# Shuttler_AFE_SAS_CON.net
KiCad netlist of a schematic drawn in Altium Designer
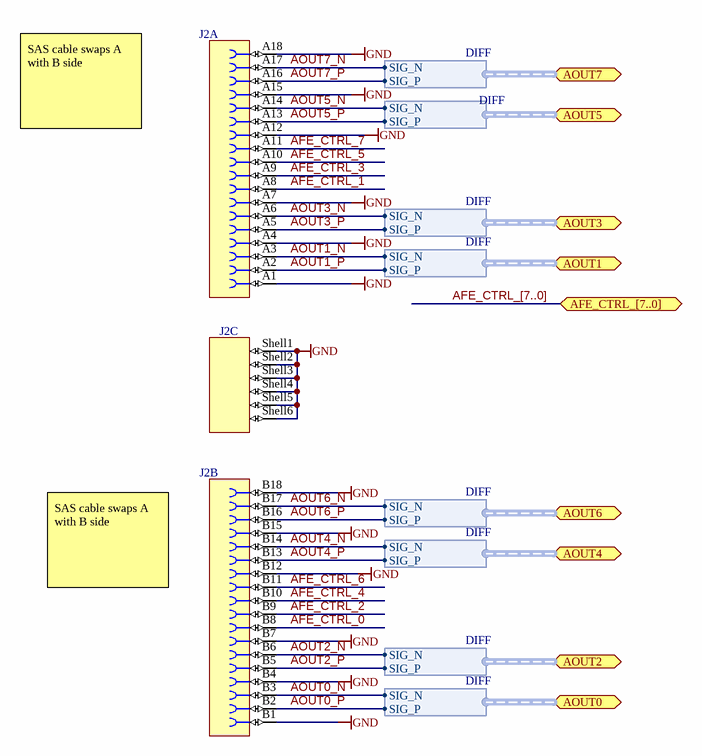
[diagram p0: Shuttler_AFE_SAS_CON.SchDoc]

(export (version "E")
  (design (tool "Eeschema 10.0.6"))
  (components
    (comp (ref "J2")
      (value "iPass™")
      (footprint "MOLEX_75783-0107")
      (fields
        (field (name "PART NUMBER") "MOLEX 75783-0107 / 75783-0136")
        (field (name "MANUFACTURER") "MOLEX")
        (field (name "MANUFACTURER PART NUMBER") "75783-0107 / 75783-0136")
        (field (name "AUTHOR") "CERN DEM JLC")
      )
      (libsource (lib "Connectors") (part "MOLEX_75783-0107"))
    )
  )
  (nets
    (net (code "2") (name "/AFE_CTRL_0") (class "Default")
      (node (ref "J2") (pin "B8") (pinfunction "B8_B8") (pintype "bidirectional"))
    )
    (net (code "3") (name "/AFE_CTRL_1") (class "Default")
      (node (ref "J2") (pin "A8") (pinfunction "A8_A8") (pintype "bidirectional"))
    )
    (net (code "4") (name "/AFE_CTRL_2") (class "Default")
      (node (ref "J2") (pin "B9") (pinfunction "B9_B9") (pintype "bidirectional"))
    )
    (net (code "5") (name "/AFE_CTRL_3") (class "Default")
      (node (ref "J2") (pin "A9") (pinfunction "A9_A9") (pintype "bidirectional"))
    )
    (net (code "6") (name "/AFE_CTRL_4") (class "Default")
      (node (ref "J2") (pin "B10") (pinfunction "B10_B10") (pintype "bidirectional"))
    )
    (net (code "7") (name "/AFE_CTRL_5") (class "Default")
      (node (ref "J2") (pin "A10") (pinfunction "A10_A10") (pintype "bidirectional"))
    )
    (net (code "8") (name "/AFE_CTRL_6") (class "Default")
      (node (ref "J2") (pin "B11") (pinfunction "B11_B11") (pintype "bidirectional"))
    )
    (net (code "9") (name "/AFE_CTRL_7") (class "Default")
      (node (ref "J2") (pin "A11") (pinfunction "A11_A11") (pintype "bidirectional"))
    )
    (net (code "11") (name "/AOUT0_N") (class "Default")
      (node (ref "J2") (pin "B3") (pinfunction "B3_B3") (pintype "bidirectional"))
    )
    (net (code "12") (name "/AOUT0_P") (class "Default")
      (node (ref "J2") (pin "B2") (pinfunction "B2_B2") (pintype "bidirectional"))
    )
    (net (code "13") (name "/AOUT1_N") (class "Default")
      (node (ref "J2") (pin "A3") (pinfunction "A3_A3") (pintype "bidirectional"))
    )
    (net (code "14") (name "/AOUT1_P") (class "Default")
      (node (ref "J2") (pin "A2") (pinfunction "A2_A2") (pintype "bidirectional"))
    )
    (net (code "15") (name "/AOUT2_N") (class "Default")
      (node (ref "J2") (pin "B6") (pinfunction "B6_B6") (pintype "bidirectional"))
    )
    (net (code "16") (name "/AOUT2_P") (class "Default")
      (node (ref "J2") (pin "B5") (pinfunction "B5_B5") (pintype "bidirectional"))
    )
    (net (code "17") (name "/AOUT3_N") (class "Default")
      (node (ref "J2") (pin "A6") (pinfunction "A6_A6") (pintype "bidirectional"))
    )
    (net (code "18") (name "/AOUT3_P") (class "Default")
      (node (ref "J2") (pin "A5") (pinfunction "A5_A5") (pintype "bidirectional"))
    )
    (net (code "19") (name "/AOUT4_N") (class "Default")
      (node (ref "J2") (pin "B14") (pinfunction "B14_B14") (pintype "bidirectional"))
    )
    (net (code "20") (name "/AOUT4_P") (class "Default")
      (node (ref "J2") (pin "B13") (pinfunction "B13_B13") (pintype "bidirectional"))
    )
    (net (code "21") (name "/AOUT5_N") (class "Default")
      (node (ref "J2") (pin "A14") (pinfunction "A14_A14") (pintype "bidirectional"))
    )
    (net (code "22") (name "/AOUT5_P") (class "Default")
      (node (ref "J2") (pin "A13") (pinfunction "A13_A13") (pintype "bidirectional"))
    )
    (net (code "23") (name "/AOUT6_N") (class "Default")
      (node (ref "J2") (pin "B17") (pinfunction "B17_B17") (pintype "bidirectional"))
    )
    (net (code "24") (name "/AOUT6_P") (class "Default")
      (node (ref "J2") (pin "B16") (pinfunction "B16_B16") (pintype "bidirectional"))
    )
    (net (code "25") (name "/AOUT7_N") (class "Default")
      (node (ref "J2") (pin "A17") (pinfunction "A17_A17") (pintype "bidirectional"))
    )
    (net (code "26") (name "/AOUT7_P") (class "Default")
      (node (ref "J2") (pin "A16") (pinfunction "A16_A16") (pintype "bidirectional"))
    )
    (net (code "28") (name "GND") (class "Default")
      (node (ref "J2") (pin "A1") (pinfunction "A1_A1") (pintype "bidirectional"))
      (node (ref "J2") (pin "A12") (pinfunction "A12_A12") (pintype "bidirectional"))
      (node (ref "J2") (pin "A15") (pinfunction "A15_A15") (pintype "bidirectional"))
      (node (ref "J2") (pin "A18") (pinfunction "A18_A18") (pintype "bidirectional"))
      (node (ref "J2") (pin "A4") (pinfunction "A4_A4") (pintype "bidirectional"))
      (node (ref "J2") (pin "A7") (pinfunction "A7_A7") (pintype "bidirectional"))
      (node (ref "J2") (pin "B1") (pinfunction "B1_B1") (pintype "bidirectional"))
      (node (ref "J2") (pin "B12") (pinfunction "B12_B12") (pintype "bidirectional"))
      (node (ref "J2") (pin "B15") (pinfunction "B15_B15") (pintype "bidirectional"))
      (node (ref "J2") (pin "B18") (pinfunction "B18_B18") (pintype "bidirectional"))
      (node (ref "J2") (pin "B4") (pinfunction "B4_B4") (pintype "bidirectional"))
      (node (ref "J2") (pin "B7") (pinfunction "B7_B7") (pintype "bidirectional"))
      (node (ref "J2") (pin "Shell1") (pinfunction "Shell1_Shell1") (pintype "bidirectional"))
      (node (ref "J2") (pin "Shell2") (pinfunction "Shell2_Shell2") (pintype "bidirectional"))
      (node (ref "J2") (pin "Shell3") (pinfunction "Shell3_Shell3") (pintype "bidirectional"))
      (node (ref "J2") (pin "Shell4") (pinfunction "Shell4_Shell4") (pintype "bidirectional"))
      (node (ref "J2") (pin "Shell5") (pinfunction "Shell5_Shell5") (pintype "bidirectional"))
      (node (ref "J2") (pin "Shell6") (pinfunction "Shell6_Shell6") (pintype "bidirectional"))
    )
  )
)
